# CLK_INPUT.net
KiCad netlist of a schematic drawn in Altium Designer
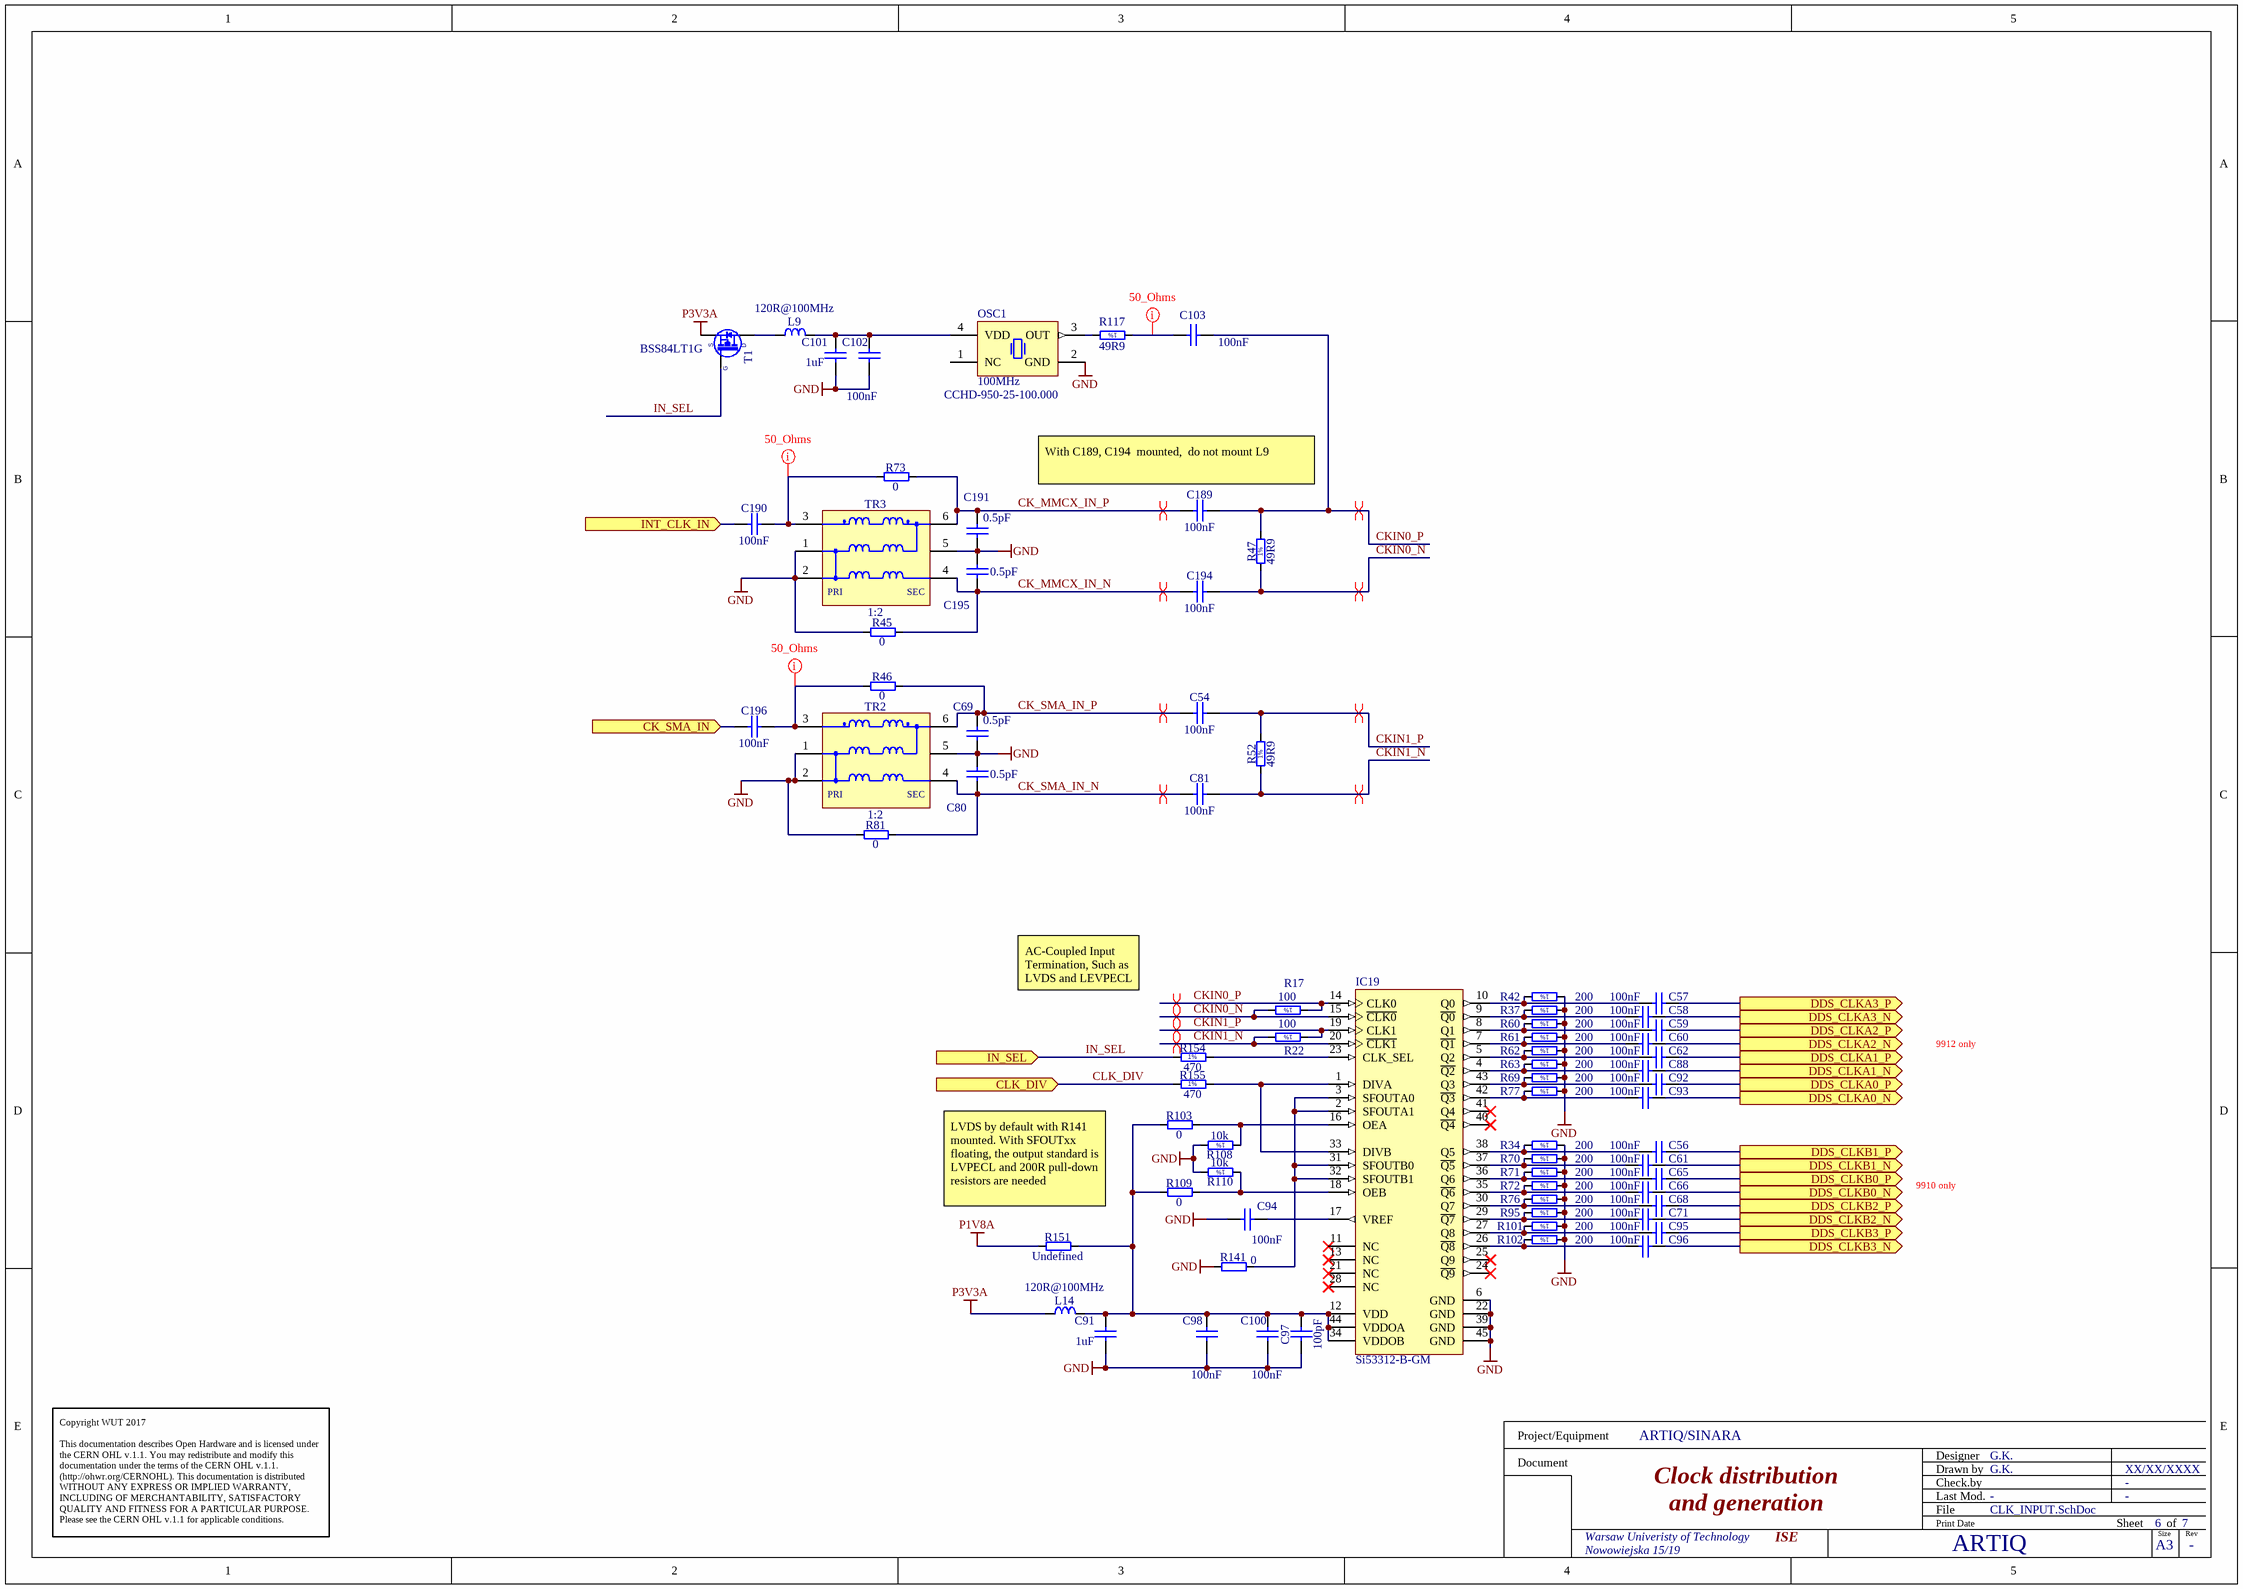
[diagram p0: CLK_INPUT.SchDoc]

(export (version "E")
  (design (tool "Eeschema 10.0.6"))
  (components
    (comp (ref "C54")
      (value "100nF")
      (footprint "CAPC1005X55N")
      (description "Non-polarised capacitor")
      (fields
        (field (name "PART NUMBER") "CC0402_100NF_16V_10%_X5R")
        (field (name "VOLTAGE") "16V")
        (field (name "AUTHOR") "CERN DEM JLC")
      )
      (libsource (lib "Capacitors") (part "Capacitor - non polarized"))
    )
    (comp (ref "C56")
      (value "100nF")
      (footprint "CAPC1005X55N")
      (description "Non-polarised capacitor")
      (fields
        (field (name "PART NUMBER") "CC0402_100NF_16V_10%_X5R")
        (field (name "VOLTAGE") "16V")
        (field (name "AUTHOR") "CERN DEM JLC")
      )
      (libsource (lib "Capacitors") (part "Capacitor - non polarized"))
    )
    (comp (ref "C57")
      (value "100nF")
      (footprint "CAPC1005X55N")
      (description "Non-polarised capacitor")
      (fields
        (field (name "PART NUMBER") "CC0402_100NF_16V_10%_X5R")
        (field (name "VOLTAGE") "16V")
        (field (name "AUTHOR") "CERN DEM JLC")
      )
      (libsource (lib "Capacitors") (part "Capacitor - non polarized"))
    )
    (comp (ref "C58")
      (value "100nF")
      (footprint "CAPC1005X55N")
      (description "Non-polarised capacitor")
      (fields
        (field (name "PART NUMBER") "CC0402_100NF_16V_10%_X5R")
        (field (name "VOLTAGE") "16V")
        (field (name "AUTHOR") "CERN DEM JLC")
      )
      (libsource (lib "Capacitors") (part "Capacitor - non polarized"))
    )
    (comp (ref "C59")
      (value "100nF")
      (footprint "CAPC1005X55N")
      (description "Non-polarised capacitor")
      (fields
        (field (name "PART NUMBER") "CC0402_100NF_16V_10%_X5R")
        (field (name "VOLTAGE") "16V")
        (field (name "AUTHOR") "CERN DEM JLC")
      )
      (libsource (lib "Capacitors") (part "Capacitor - non polarized"))
    )
    (comp (ref "C60")
      (value "100nF")
      (footprint "CAPC1005X55N")
      (description "Non-polarised capacitor")
      (fields
        (field (name "PART NUMBER") "CC0402_100NF_16V_10%_X5R")
        (field (name "VOLTAGE") "16V")
        (field (name "AUTHOR") "CERN DEM JLC")
      )
      (libsource (lib "Capacitors") (part "Capacitor - non polarized"))
    )
    (comp (ref "C61")
      (value "100nF")
      (footprint "CAPC1005X55N")
      (description "Non-polarised capacitor")
      (fields
        (field (name "PART NUMBER") "CC0402_100NF_16V_10%_X5R")
        (field (name "VOLTAGE") "16V")
        (field (name "AUTHOR") "CERN DEM JLC")
      )
      (libsource (lib "Capacitors") (part "Capacitor - non polarized"))
    )
    (comp (ref "C62")
      (value "100nF")
      (footprint "CAPC1005X55N")
      (description "Non-polarised capacitor")
      (fields
        (field (name "PART NUMBER") "CC0402_100NF_16V_10%_X5R")
        (field (name "VOLTAGE") "16V")
        (field (name "AUTHOR") "CERN DEM JLC")
      )
      (libsource (lib "Capacitors") (part "Capacitor - non polarized"))
    )
    (comp (ref "C65")
      (value "100nF")
      (footprint "CAPC1005X55N")
      (description "Non-polarised capacitor")
      (fields
        (field (name "PART NUMBER") "CC0402_100NF_16V_10%_X5R")
        (field (name "VOLTAGE") "16V")
        (field (name "AUTHOR") "CERN DEM JLC")
      )
      (libsource (lib "Capacitors") (part "Capacitor - non polarized"))
    )
    (comp (ref "C66")
      (value "100nF")
      (footprint "CAPC1005X55N")
      (description "Non-polarised capacitor")
      (fields
        (field (name "PART NUMBER") "CC0402_100NF_16V_10%_X5R")
        (field (name "VOLTAGE") "16V")
        (field (name "AUTHOR") "CERN DEM JLC")
      )
      (libsource (lib "Capacitors") (part "Capacitor - non polarized"))
    )
    (comp (ref "C68")
      (value "100nF")
      (footprint "CAPC1005X55N")
      (description "Non-polarised capacitor")
      (fields
        (field (name "PART NUMBER") "CC0402_100NF_16V_10%_X5R")
        (field (name "VOLTAGE") "16V")
        (field (name "AUTHOR") "CERN DEM JLC")
      )
      (libsource (lib "Capacitors") (part "Capacitor - non polarized"))
    )
    (comp (ref "C69")
      (value "0.5pF")
      (footprint "CAPC1005X50N")
      (description "Non-polarised capacitor")
      (fields
        (field (name "PART NUMBER") "CC0402_0.5PF_25V_0.05PF_AVX_04023J0R5ABSTR")
        (field (name "VOLTAGE") "25V")
        (field (name "AUTHOR") "CERN DEM JLC")
      )
      (libsource (lib "Capacitors") (part "Capacitor - non polarized"))
    )
    (comp (ref "C71")
      (value "100nF")
      (footprint "CAPC1005X55N")
      (description "Non-polarised capacitor")
      (fields
        (field (name "PART NUMBER") "CC0402_100NF_16V_10%_X5R")
        (field (name "VOLTAGE") "16V")
        (field (name "AUTHOR") "CERN DEM JLC")
      )
      (libsource (lib "Capacitors") (part "Capacitor - non polarized"))
    )
    (comp (ref "C80")
      (value "0.5pF")
      (footprint "CAPC1005X50N")
      (description "Non-polarised capacitor")
      (fields
        (field (name "PART NUMBER") "CC0402_0.5PF_25V_0.05PF_AVX_04023J0R5ABSTR")
        (field (name "VOLTAGE") "25V")
        (field (name "AUTHOR") "CERN DEM JLC")
      )
      (libsource (lib "Capacitors") (part "Capacitor - non polarized"))
    )
    (comp (ref "C81")
      (value "100nF")
      (footprint "CAPC1005X55N")
      (description "Non-polarised capacitor")
      (fields
        (field (name "PART NUMBER") "CC0402_100NF_16V_10%_X5R")
        (field (name "VOLTAGE") "16V")
        (field (name "AUTHOR") "CERN DEM JLC")
      )
      (libsource (lib "Capacitors") (part "Capacitor - non polarized"))
    )
    (comp (ref "C88")
      (value "100nF")
      (footprint "CAPC1005X55N")
      (description "Non-polarised capacitor")
      (fields
        (field (name "PART NUMBER") "CC0402_100NF_16V_10%_X5R")
        (field (name "VOLTAGE") "16V")
        (field (name "AUTHOR") "CERN DEM JLC")
      )
      (libsource (lib "Capacitors") (part "Capacitor - non polarized"))
    )
    (comp (ref "C91")
      (value "1uF")
      (footprint "CAPC1005X55N")
      (description "Non-polarised capacitor")
      (fields
        (field (name "PART NUMBER") "CC0402_1UF_16V_10%_X5R")
        (field (name "VOLTAGE") "16V")
        (field (name "AUTHOR") "CERN DEM JLC")
      )
      (libsource (lib "Capacitors") (part "Capacitor - non polarized"))
    )
    (comp (ref "C92")
      (value "100nF")
      (footprint "CAPC1005X55N")
      (description "Non-polarised capacitor")
      (fields
        (field (name "PART NUMBER") "CC0402_100NF_16V_10%_X5R")
        (field (name "VOLTAGE") "16V")
        (field (name "AUTHOR") "CERN DEM JLC")
      )
      (libsource (lib "Capacitors") (part "Capacitor - non polarized"))
    )
    (comp (ref "C93")
      (value "100nF")
      (footprint "CAPC1005X55N")
      (description "Non-polarised capacitor")
      (fields
        (field (name "PART NUMBER") "CC0402_100NF_16V_10%_X5R")
        (field (name "VOLTAGE") "16V")
        (field (name "AUTHOR") "CERN DEM JLC")
      )
      (libsource (lib "Capacitors") (part "Capacitor - non polarized"))
    )
    (comp (ref "C94")
      (value "100nF")
      (footprint "CAPC1005X55N")
      (description "Non-polarised capacitor")
      (fields
        (field (name "PART NUMBER") "CC0402_100NF_16V_10%_X5R")
        (field (name "VOLTAGE") "16V")
        (field (name "AUTHOR") "CERN DEM JLC")
      )
      (libsource (lib "Capacitors") (part "Capacitor - non polarized"))
    )
    (comp (ref "C95")
      (value "100nF")
      (footprint "CAPC1005X55N")
      (description "Non-polarised capacitor")
      (fields
        (field (name "PART NUMBER") "CC0402_100NF_16V_10%_X5R")
        (field (name "VOLTAGE") "16V")
        (field (name "AUTHOR") "CERN DEM JLC")
      )
      (libsource (lib "Capacitors") (part "Capacitor - non polarized"))
    )
    (comp (ref "C96")
      (value "100nF")
      (footprint "CAPC1005X55N")
      (description "Non-polarised capacitor")
      (fields
        (field (name "PART NUMBER") "CC0402_100NF_16V_10%_X5R")
        (field (name "VOLTAGE") "16V")
        (field (name "AUTHOR") "CERN DEM JLC")
      )
      (libsource (lib "Capacitors") (part "Capacitor - non polarized"))
    )
    (comp (ref "C97")
      (value "100pF")
      (footprint "CAPC1005X55N")
      (description "Non-polarised capacitor")
      (fields
        (field (name "PART NUMBER") "CC0402_100PF_50V_5%_C0G")
        (field (name "VOLTAGE") "50V")
        (field (name "AUTHOR") "CERN DEM JLC")
      )
      (libsource (lib "Capacitors") (part "Capacitor - non polarized"))
    )
    (comp (ref "C98")
      (value "100nF")
      (footprint "CAPC1005X55N")
      (description "Non-polarised capacitor")
      (fields
        (field (name "PART NUMBER") "CC0402_100NF_16V_10%_X5R")
        (field (name "VOLTAGE") "16V")
        (field (name "AUTHOR") "CERN DEM JLC")
      )
      (libsource (lib "Capacitors") (part "Capacitor - non polarized"))
    )
    (comp (ref "C100")
      (value "100nF")
      (footprint "CAPC1005X55N")
      (description "Non-polarised capacitor")
      (fields
        (field (name "PART NUMBER") "CC0402_100NF_16V_10%_X5R")
        (field (name "VOLTAGE") "16V")
        (field (name "AUTHOR") "CERN DEM JLC")
      )
      (libsource (lib "Capacitors") (part "Capacitor - non polarized"))
    )
    (comp (ref "C101")
      (value "1uF")
      (footprint "CAPC1005X55N")
      (description "Non-polarised capacitor")
      (fields
        (field (name "PART NUMBER") "CC0402_1UF_16V_10%_X5R")
        (field (name "VOLTAGE") "16V")
        (field (name "AUTHOR") "CERN DEM JLC")
      )
      (libsource (lib "Capacitors") (part "Capacitor - non polarized"))
    )
    (comp (ref "C102")
      (value "100nF")
      (footprint "CAPC1005X55N")
      (description "Non-polarised capacitor")
      (fields
        (field (name "PART NUMBER") "CC0402_100NF_16V_10%_X5R")
        (field (name "VOLTAGE") "16V")
        (field (name "AUTHOR") "CERN DEM JLC")
      )
      (libsource (lib "Capacitors") (part "Capacitor - non polarized"))
    )
    (comp (ref "C103")
      (value "100nF")
      (footprint "CAPC1005X55N")
      (description "Non-polarised capacitor")
      (fields
        (field (name "PART NUMBER") "CC0402_100NF_16V_10%_X5R")
        (field (name "VOLTAGE") "16V")
        (field (name "AUTHOR") "CERN DEM JLC")
      )
      (libsource (lib "Capacitors") (part "Capacitor - non polarized"))
    )
    (comp (ref "C189")
      (value "100nF")
      (footprint "CAPC1005X55N")
      (description "Non-polarised capacitor")
      (fields
        (field (name "PART NUMBER") "CC0402_100NF_16V_10%_X5R")
        (field (name "VOLTAGE") "16V")
        (field (name "AUTHOR") "CERN DEM JLC")
      )
      (libsource (lib "Capacitors") (part "Capacitor - non polarized"))
    )
    (comp (ref "C190")
      (value "100nF")
      (footprint "CAPC1005X55N")
      (description "Non-polarised capacitor")
      (fields
        (field (name "PART NUMBER") "CC0402_100NF_16V_10%_X5R")
        (field (name "VOLTAGE") "16V")
        (field (name "AUTHOR") "CERN DEM JLC")
      )
      (libsource (lib "Capacitors") (part "Capacitor - non polarized"))
    )
    (comp (ref "C191")
      (value "0.5pF")
      (footprint "CAPC1005X50N")
      (description "Non-polarised capacitor")
      (fields
        (field (name "PART NUMBER") "CC0402_0.5PF_25V_0.05PF_AVX_04023J0R5ABSTR")
        (field (name "VOLTAGE") "25V")
        (field (name "AUTHOR") "CERN DEM JLC")
      )
      (libsource (lib "Capacitors") (part "Capacitor - non polarized"))
    )
    (comp (ref "C194")
      (value "100nF")
      (footprint "CAPC1005X55N")
      (description "Non-polarised capacitor")
      (fields
        (field (name "PART NUMBER") "CC0402_100NF_16V_10%_X5R")
        (field (name "VOLTAGE") "16V")
        (field (name "AUTHOR") "CERN DEM JLC")
      )
      (libsource (lib "Capacitors") (part "Capacitor - non polarized"))
    )
    (comp (ref "C195")
      (value "0.5pF")
      (footprint "CAPC1005X50N")
      (description "Non-polarised capacitor")
      (fields
        (field (name "PART NUMBER") "CC0402_0.5PF_25V_0.05PF_AVX_04023J0R5ABSTR")
        (field (name "VOLTAGE") "25V")
        (field (name "AUTHOR") "CERN DEM JLC")
      )
      (libsource (lib "Capacitors") (part "Capacitor - non polarized"))
    )
    (comp (ref "C196")
      (value "100nF")
      (footprint "CAPC1005X55N")
      (description "Non-polarised capacitor")
      (fields
        (field (name "PART NUMBER") "CC0402_100NF_16V_10%_X5R")
        (field (name "VOLTAGE") "16V")
        (field (name "AUTHOR") "CERN DEM JLC")
      )
      (libsource (lib "Capacitors") (part "Capacitor - non polarized"))
    )
    (comp (ref "IC19")
      (value "Si53312-B-GM")
      (footprint "SLAB-QFN-44-2800x2800TP_N")
      (fields (field (name "MANUFACTURER") "Silicon Labs"))
      (libsource (lib "Altium Content Vault") (part "SLAB-Si53312-QFN-44-45"))
    )
    (comp (ref "L9")
      (value "120R@100MHz")
      (footprint "INDC1608X95N")
      (description "Inductor")
      (fields
        (field (name "PART NUMBER") "IND0603_MURATA_BLM18PG121SN1D")
        (field (name "POWER") "2A")
        (field (name "AUTHOR") "CERN DEM BC")
      )
      (libsource (lib "Inductors & Transformers") (part "Inductor"))
    )
    (comp (ref "L14")
      (value "120R@100MHz")
      (footprint "INDC1608X95N")
      (description "Inductor")
      (fields
        (field (name "PART NUMBER") "IND0603_MURATA_BLM18PG121SN1D")
        (field (name "POWER") "2A")
        (field (name "AUTHOR") "CERN DEM BC")
      )
      (libsource (lib "Inductors & Transformers") (part "Inductor"))
    )
    (comp (ref "OSC1")
      (value "100MHz")
      (footprint "OSC_CRYSTEK_CCHD-950")
      (description "100MHz low noise oscillator")
      (fields
        (field (name "PART NUMBER") "OSC_100MHZ_CRYSTEK_CCHD-950-25-100.000")
        (field (name "MANUFACTURER") "CRYSTEK CRYSTAL")
        (field (name "MANUFACTURER PART NUMBER") "CCHD-950-25-100.000")
        (field (name "AUTHOR") "GK")
      )
      (libsource (lib "LIBRARY_SCH") (part "OSC_CCHD-950"))
    )
    (comp (ref "R17")
      (value "100")
      (footprint "RESC1005X40N")
      (description "Resistor - 1%")
      (fields
        (field (name "PART NUMBER") "R0402_100R_1%_0.0625W_100PPM")
        (field (name "POWER") "0.0625W")
        (field (name "AUTHOR") "CERN DEM JLC")
      )
      (libsource (lib "Resistors") (part "Resistor - 1%"))
    )
    (comp (ref "R22")
      (value "100")
      (footprint "RESC1005X40N")
      (description "Resistor - 1%")
      (fields
        (field (name "PART NUMBER") "R0402_100R_1%_0.0625W_100PPM")
        (field (name "POWER") "0.0625W")
        (field (name "AUTHOR") "CERN DEM JLC")
      )
      (libsource (lib "Resistors") (part "Resistor - 1%"))
    )
    (comp (ref "R34")
      (value "200")
      (footprint "RESC1005X40N")
      (description "Resistor - 1%")
      (fields
        (field (name "PART NUMBER") "R0402_200R_1%_0.0625W_100PPM")
        (field (name "POWER") "0.0625W")
        (field (name "AUTHOR") "CERN DEM JLC")
      )
      (libsource (lib "Resistors") (part "Resistor - 1%"))
    )
    (comp (ref "R37")
      (value "200")
      (footprint "RESC1005X40N")
      (description "Resistor - 1%")
      (fields
        (field (name "PART NUMBER") "R0402_200R_1%_0.0625W_100PPM")
        (field (name "POWER") "0.0625W")
        (field (name "AUTHOR") "CERN DEM JLC")
      )
      (libsource (lib "Resistors") (part "Resistor - 1%"))
    )
    (comp (ref "R42")
      (value "200")
      (footprint "RESC1005X40N")
      (description "Resistor - 1%")
      (fields
        (field (name "PART NUMBER") "R0402_200R_1%_0.0625W_100PPM")
        (field (name "POWER") "0.0625W")
        (field (name "AUTHOR") "CERN DEM JLC")
      )
      (libsource (lib "Resistors") (part "Resistor - 1%"))
    )
    (comp (ref "R45")
      (value "0")
      (footprint "RESC1005X40N")
      (description "Resistor")
      (fields
        (field (name "PART NUMBER") "R0402_0R_JUMPER")
        (field (name "MANUFACTURER") "GENERIC")
        (field (name "AUTHOR") "CERN DEM JLC")
      )
      (libsource (lib "Resistors") (part "Resistor"))
    )
    (comp (ref "R46")
      (value "0")
      (footprint "RESC1005X40N")
      (description "Resistor")
      (fields
        (field (name "PART NUMBER") "R0402_0R_JUMPER")
        (field (name "MANUFACTURER") "GENERIC")
        (field (name "AUTHOR") "CERN DEM JLC")
      )
      (libsource (lib "Resistors") (part "Resistor"))
    )
    (comp (ref "R47")
      (value "49R9")
      (footprint "RESC1005X40N")
      (description "Resistor - 1%")
      (fields
        (field (name "PART NUMBER") "R0402_49R9_1%_0.0625W_100PPM")
        (field (name "POWER") "0.0625W")
        (field (name "AUTHOR") "CERN DEM JLC")
      )
      (libsource (lib "Resistors") (part "Resistor - 1%"))
    )
    (comp (ref "R52")
      (value "49R9")
      (footprint "RESC1005X40N")
      (description "Resistor - 1%")
      (fields
        (field (name "PART NUMBER") "R0402_49R9_1%_0.0625W_100PPM")
        (field (name "POWER") "0.0625W")
        (field (name "AUTHOR") "CERN DEM JLC")
      )
      (libsource (lib "Resistors") (part "Resistor - 1%"))
    )
    (comp (ref "R60")
      (value "200")
      (footprint "RESC1005X40N")
      (description "Resistor - 1%")
      (fields
        (field (name "PART NUMBER") "R0402_200R_1%_0.0625W_100PPM")
        (field (name "POWER") "0.0625W")
        (field (name "AUTHOR") "CERN DEM JLC")
      )
      (libsource (lib "Resistors") (part "Resistor - 1%"))
    )
    (comp (ref "R61")
      (value "200")
      (footprint "RESC1005X40N")
      (description "Resistor - 1%")
      (fields
        (field (name "PART NUMBER") "R0402_200R_1%_0.0625W_100PPM")
        (field (name "POWER") "0.0625W")
        (field (name "AUTHOR") "CERN DEM JLC")
      )
      (libsource (lib "Resistors") (part "Resistor - 1%"))
    )
    (comp (ref "R62")
      (value "200")
      (footprint "RESC1005X40N")
      (description "Resistor - 1%")
      (fields
        (field (name "PART NUMBER") "R0402_200R_1%_0.0625W_100PPM")
        (field (name "POWER") "0.0625W")
        (field (name "AUTHOR") "CERN DEM JLC")
      )
      (libsource (lib "Resistors") (part "Resistor - 1%"))
    )
    (comp (ref "R63")
      (value "200")
      (footprint "RESC1005X40N")
      (description "Resistor - 1%")
      (fields
        (field (name "PART NUMBER") "R0402_200R_1%_0.0625W_100PPM")
        (field (name "POWER") "0.0625W")
        (field (name "AUTHOR") "CERN DEM JLC")
      )
      (libsource (lib "Resistors") (part "Resistor - 1%"))
    )
    (comp (ref "R69")
      (value "200")
      (footprint "RESC1005X40N")
      (description "Resistor - 1%")
      (fields
        (field (name "PART NUMBER") "R0402_200R_1%_0.0625W_100PPM")
        (field (name "POWER") "0.0625W")
        (field (name "AUTHOR") "CERN DEM JLC")
      )
      (libsource (lib "Resistors") (part "Resistor - 1%"))
    )
    (comp (ref "R70")
      (value "200")
      (footprint "RESC1005X40N")
      (description "Resistor - 1%")
      (fields
        (field (name "PART NUMBER") "R0402_200R_1%_0.0625W_100PPM")
        (field (name "POWER") "0.0625W")
        (field (name "AUTHOR") "CERN DEM JLC")
      )
      (libsource (lib "Resistors") (part "Resistor - 1%"))
    )
    (comp (ref "R71")
      (value "200")
      (footprint "RESC1005X40N")
      (description "Resistor - 1%")
      (fields
        (field (name "PART NUMBER") "R0402_200R_1%_0.0625W_100PPM")
        (field (name "POWER") "0.0625W")
        (field (name "AUTHOR") "CERN DEM JLC")
      )
      (libsource (lib "Resistors") (part "Resistor - 1%"))
    )
    (comp (ref "R72")
      (value "200")
      (footprint "RESC1005X40N")
      (description "Resistor - 1%")
      (fields
        (field (name "PART NUMBER") "R0402_200R_1%_0.0625W_100PPM")
        (field (name "POWER") "0.0625W")
        (field (name "AUTHOR") "CERN DEM JLC")
      )
      (libsource (lib "Resistors") (part "Resistor - 1%"))
    )
    (comp (ref "R73")
      (value "0")
      (footprint "RESC1005X40N")
      (description "Resistor")
      (fields
        (field (name "PART NUMBER") "R0402_0R_JUMPER")
        (field (name "MANUFACTURER") "GENERIC")
        (field (name "AUTHOR") "CERN DEM JLC")
      )
      (libsource (lib "Resistors") (part "Resistor"))
    )
    (comp (ref "R76")
      (value "200")
      (footprint "RESC1005X40N")
      (description "Resistor - 1%")
      (fields
        (field (name "PART NUMBER") "R0402_200R_1%_0.0625W_100PPM")
        (field (name "POWER") "0.0625W")
        (field (name "AUTHOR") "CERN DEM JLC")
      )
      (libsource (lib "Resistors") (part "Resistor - 1%"))
    )
    (comp (ref "R77")
      (value "200")
      (footprint "RESC1005X40N")
      (description "Resistor - 1%")
      (fields
        (field (name "PART NUMBER") "R0402_200R_1%_0.0625W_100PPM")
        (field (name "POWER") "0.0625W")
        (field (name "AUTHOR") "CERN DEM JLC")
      )
      (libsource (lib "Resistors") (part "Resistor - 1%"))
    )
    (comp (ref "R81")
      (value "0")
      (footprint "RESC1005X40N")
      (description "Resistor")
      (fields
        (field (name "PART NUMBER") "R0402_0R_JUMPER")
        (field (name "MANUFACTURER") "GENERIC")
        (field (name "AUTHOR") "CERN DEM JLC")
      )
      (libsource (lib "Resistors") (part "Resistor"))
    )
    (comp (ref "R95")
      (value "200")
      (footprint "RESC1005X40N")
      (description "Resistor - 1%")
      (fields
        (field (name "PART NUMBER") "R0402_200R_1%_0.0625W_100PPM")
        (field (name "POWER") "0.0625W")
        (field (name "AUTHOR") "CERN DEM JLC")
      )
      (libsource (lib "Resistors") (part "Resistor - 1%"))
    )
    (comp (ref "R101")
      (value "200")
      (footprint "RESC1005X40N")
      (description "Resistor - 1%")
      (fields
        (field (name "PART NUMBER") "R0402_200R_1%_0.0625W_100PPM")
        (field (name "POWER") "0.0625W")
        (field (name "AUTHOR") "CERN DEM JLC")
      )
      (libsource (lib "Resistors") (part "Resistor - 1%"))
    )
    (comp (ref "R102")
      (value "200")
      (footprint "RESC1005X40N")
      (description "Resistor - 1%")
      (fields
        (field (name "PART NUMBER") "R0402_200R_1%_0.0625W_100PPM")
        (field (name "POWER") "0.0625W")
        (field (name "AUTHOR") "CERN DEM JLC")
      )
      (libsource (lib "Resistors") (part "Resistor - 1%"))
    )
    (comp (ref "R103")
      (value "0")
      (footprint "RESC1608X55N")
      (description "Resistor")
      (fields
        (field (name "PART NUMBER") "R0603_0R_JUMPER")
        (field (name "MANUFACTURER") "GENERIC")
        (field (name "AUTHOR") "CERN DEM JLC")
      )
      (libsource (lib "Resistors") (part "Resistor"))
    )
    (comp (ref "R108")
      (value "10k")
      (footprint "RESC1005X40N")
      (description "Resistor - 1%")
      (fields
        (field (name "PART NUMBER") "R0402_10K_1%_0.0625W_100PPM")
        (field (name "POWER") "0.0625W")
        (field (name "AUTHOR") "CERN DEM JLC")
      )
      (libsource (lib "Resistors") (part "Resistor - 1%"))
    )
    (comp (ref "R109")
      (value "0")
      (footprint "RESC1608X55N")
      (description "Resistor")
      (fields
        (field (name "PART NUMBER") "R0603_0R_JUMPER")
        (field (name "MANUFACTURER") "GENERIC")
        (field (name "AUTHOR") "CERN DEM JLC")
      )
      (libsource (lib "Resistors") (part "Resistor"))
    )
    (comp (ref "R110")
      (value "10k")
      (footprint "RESC1005X40N")
      (description "Resistor - 1%")
      (fields
        (field (name "PART NUMBER") "R0402_10K_1%_0.0625W_100PPM")
        (field (name "POWER") "0.0625W")
        (field (name "AUTHOR") "CERN DEM JLC")
      )
      (libsource (lib "Resistors") (part "Resistor - 1%"))
    )
    (comp (ref "R117")
      (value "49R9")
      (footprint "RESC1005X40N")
      (description "Resistor - 1%")
      (fields
        (field (name "PART NUMBER") "R0402_49R9_1%_0.0625W_100PPM")
        (field (name "POWER") "0.0625W")
        (field (name "AUTHOR") "CERN DEM JLC")
      )
      (libsource (lib "Resistors") (part "Resistor - 1%"))
    )
    (comp (ref "R141")
      (value "0")
      (footprint "RESC1608X55N")
      (description "Resistor")
      (fields
        (field (name "PART NUMBER") "R0603_0R_JUMPER")
        (field (name "MANUFACTURER") "GENERIC")
        (field (name "AUTHOR") "CERN DEM JLC")
      )
      (libsource (lib "Resistors") (part "Resistor"))
    )
    (comp (ref "R151")
      (value "Undefined")
      (footprint "RESC1608X55N")
      (description "Resistor")
      (fields (field (name "PART NUMBER") "R0603_NO-VALUE") (field (name "AUTHOR") "CERN DEM JLC"))
      (libsource (lib "Resistors") (part "Resistor"))
    )
    (comp (ref "R154")
      (value "470")
      (footprint "RESC1005X40N")
      (description "Resistor - 1%")
      (fields
        (field (name "PART NUMBER") "R0402_470R_1%_0.0625W_100PPM")
        (field (name "POWER") "0.0625W")
        (field (name "AUTHOR") "CERN DEM JLC")
      )
      (libsource (lib "Resistors") (part "Resistor - 1%"))
    )
    (comp (ref "R155")
      (value "470")
      (footprint "RESC1005X40N")
      (description "Resistor - 1%")
      (fields
        (field (name "PART NUMBER") "R0402_470R_1%_0.0625W_100PPM")
        (field (name "POWER") "0.0625W")
        (field (name "AUTHOR") "CERN DEM JLC")
      )
      (libsource (lib "Resistors") (part "Resistor - 1%"))
    )
    (comp (ref "T1")
      (value "BSS84LT1G")
      (footprint "SOT95P240X110-3N")
      (description "P-CHANNEL MOSFET WITH DIODE")
      (fields (field (name "MANUFACTURER") "ON SEMICONDUCTOR") (field (name "AUTHOR") "CERN DEM JLC"))
      (libsource (lib "ICs And Semiconductors") (part "P-MOSFET-D 1G 2S 3D"))
    )
    (comp (ref "TR2")
      (value "1:2")
      (footprint "XFMR_MINI-CIRCUITS_DB1627")
      (description "50 OHMS 10 to 4000 MHz RF Transformer")
      (fields
        (field (name "PART NUMBER") "XFMR_MINI-CIRCUITS_TCM2-43X+")
        (field (name "POWER") "0.4W")
        (field (name "AUTHOR") "CERN DEM BC")
      )
      (libsource (lib "Inductors & Transformers") (part "XFMR_MINI-CIRCUITS_TCM2-43X"))
    )
    (comp (ref "TR3")
      (value "1:2")
      (footprint "XFMR_MINI-CIRCUITS_DB1627")
      (description "50 OHMS 10 to 4000 MHz RF Transformer")
      (fields
        (field (name "PART NUMBER") "XFMR_MINI-CIRCUITS_TCM2-43X+")
        (field (name "POWER") "0.4W")
        (field (name "AUTHOR") "CERN DEM BC")
      )
      (libsource (lib "Inductors & Transformers") (part "XFMR_MINI-CIRCUITS_TCM2-43X"))
    )
  )
  (nets
    (net (code "1") (name "/CKIN0_N") (class "Default")
      (node (ref "C194") (pin "2") (pinfunction "2_2") (pintype "passive"))
      (node (ref "IC19") (pin "15") (pinfunction "~{CLK0}_15") (pintype "input"))
      (node (ref "R17") (pin "2") (pinfunction "2_2") (pintype "passive"))
      (node (ref "R47") (pin "1") (pinfunction "1_1") (pintype "passive"))
    )
    (net (code "2") (name "/CKIN0_P") (class "Default")
      (node (ref "C103") (pin "1") (pinfunction "1_1") (pintype "passive"))
      (node (ref "C189") (pin "2") (pinfunction "2_2") (pintype "passive"))
      (node (ref "IC19") (pin "14") (pinfunction "CLK0_14") (pintype "input"))
      (node (ref "R17") (pin "1") (pinfunction "1_1") (pintype "passive"))
      (node (ref "R47") (pin "2") (pinfunction "2_2") (pintype "passive"))
    )
    (net (code "3") (name "/CKIN1_N") (class "Default")
      (node (ref "C81") (pin "2") (pinfunction "2_2") (pintype "passive"))
      (node (ref "IC19") (pin "20") (pinfunction "~{CLK1}_20") (pintype "input"))
      (node (ref "R22") (pin "2") (pinfunction "2_2") (pintype "passive"))
      (node (ref "R52") (pin "1") (pinfunction "1_1") (pintype "passive"))
    )
    (net (code "4") (name "/CKIN1_P") (class "Default")
      (node (ref "C54") (pin "2") (pinfunction "2_2") (pintype "passive"))
      (node (ref "IC19") (pin "19") (pinfunction "CLK1_19") (pintype "input"))
      (node (ref "R22") (pin "1") (pinfunction "1_1") (pintype "passive"))
      (node (ref "R52") (pin "2") (pinfunction "2_2") (pintype "passive"))
    )
    (net (code "5") (name "/CK_MMCX_IN_N") (class "Default")
      (node (ref "C194") (pin "1") (pinfunction "1_1") (pintype "passive"))
      (node (ref "C195") (pin "1") (pinfunction "1_1") (pintype "passive"))
      (node (ref "R45") (pin "2") (pinfunction "2_2") (pintype "passive"))
      (node (ref "TR3") (pin "4") (pinfunction "S1_4") (pintype "passive"))
    )
    (net (code "6") (name "/CK_MMCX_IN_P") (class "Default")
      (node (ref "C189") (pin "1") (pinfunction "1_1") (pintype "passive"))
      (node (ref "C191") (pin "2") (pinfunction "2_2") (pintype "passive"))
      (node (ref "R73") (pin "2") (pinfunction "2_2") (pintype "passive"))
      (node (ref "TR3") (pin "6") (pinfunction "S1_6") (pintype "passive"))
    )
    (net (code "7") (name "/CK_SMA_IN") (class "Default")
      (node (ref "C196") (pin "1") (pinfunction "1_1") (pintype "passive"))
    )
    (net (code "8") (name "/CK_SMA_IN_N") (class "Default")
      (node (ref "C80") (pin "1") (pinfunction "1_1") (pintype "passive"))
      (node (ref "C81") (pin "1") (pinfunction "1_1") (pintype "passive"))
      (node (ref "R81") (pin "2") (pinfunction "2_2") (pintype "passive"))
      (node (ref "TR2") (pin "4") (pinfunction "S1_4") (pintype "passive"))
    )
    (net (code "9") (name "/CK_SMA_IN_P") (class "Default")
      (node (ref "C54") (pin "1") (pinfunction "1_1") (pintype "passive"))
      (node (ref "C69") (pin "2") (pinfunction "2_2") (pintype "passive"))
      (node (ref "R46") (pin "2") (pinfunction "2_2") (pintype "passive"))
      (node (ref "TR2") (pin "6") (pinfunction "S1_6") (pintype "passive"))
    )
    (net (code "10") (name "/CLK_DIV") (class "Default")
      (node (ref "R155") (pin "1") (pinfunction "1_1") (pintype "passive"))
    )
    (net (code "11") (name "/DDS_CLKA0_N") (class "Default")
      (node (ref "C93") (pin "1") (pinfunction "1_1") (pintype "passive"))
    )
    (net (code "12") (name "/DDS_CLKA0_P") (class "Default")
      (node (ref "C92") (pin "1") (pinfunction "1_1") (pintype "passive"))
    )
    (net (code "13") (name "/DDS_CLKA1_N") (class "Default")
      (node (ref "C88") (pin "1") (pinfunction "1_1") (pintype "passive"))
    )
    (net (code "14") (name "/DDS_CLKA1_P") (class "Default")
      (node (ref "C62") (pin "1") (pinfunction "1_1") (pintype "passive"))
    )
    (net (code "15") (name "/DDS_CLKA2_N") (class "Default")
      (node (ref "C60") (pin "1") (pinfunction "1_1") (pintype "passive"))
    )
    (net (code "16") (name "/DDS_CLKA2_P") (class "Default")
      (node (ref "C59") (pin "1") (pinfunction "1_1") (pintype "passive"))
    )
    (net (code "17") (name "/DDS_CLKA3_N") (class "Default")
      (node (ref "C58") (pin "1") (pinfunction "1_1") (pintype "passive"))
    )
    (net (code "18") (name "/DDS_CLKA3_P") (class "Default")
      (node (ref "C57") (pin "1") (pinfunction "1_1") (pintype "passive"))
    )
    (net (code "19") (name "/DDS_CLKB0_N") (class "Default")
      (node (ref "C66") (pin "1") (pinfunction "1_1") (pintype "passive"))
    )
    (net (code "20") (name "/DDS_CLKB0_P") (class "Default")
      (node (ref "C65") (pin "1") (pinfunction "1_1") (pintype "passive"))
    )
    (net (code "21") (name "/DDS_CLKB1_N") (class "Default")
      (node (ref "C61") (pin "1") (pinfunction "1_1") (pintype "passive"))
    )
    (net (code "22") (name "/DDS_CLKB1_P") (class "Default")
      (node (ref "C56") (pin "1") (pinfunction "1_1") (pintype "passive"))
    )
    (net (code "23") (name "/DDS_CLKB2_N") (class "Default")
      (node (ref "C71") (pin "1") (pinfunction "1_1") (pintype "passive"))
    )
    (net (code "24") (name "/DDS_CLKB2_P") (class "Default")
      (node (ref "C68") (pin "1") (pinfunction "1_1") (pintype "passive"))
    )
    (net (code "25") (name "/DDS_CLKB3_N") (class "Default")
      (node (ref "C96") (pin "1") (pinfunction "1_1") (pintype "passive"))
    )
    (net (code "26") (name "/DDS_CLKB3_P") (class "Default")
      (node (ref "C95") (pin "1") (pinfunction "1_1") (pintype "passive"))
    )
    (net (code "27") (name "/INT_CLK_IN") (class "Default")
      (node (ref "C190") (pin "1") (pinfunction "1_1") (pintype "passive"))
    )
    (net (code "28") (name "/IN_SEL") (class "Default")
      (node (ref "R154") (pin "1") (pinfunction "1_1") (pintype "passive"))
      (node (ref "T1") (pin "1") (pinfunction "G_1") (pintype "passive"))
    )
    (net (code "29") (name "GND") (class "Default")
      (node (ref "C100") (pin "1") (pinfunction "1_1") (pintype "passive"))
      (node (ref "C101") (pin "1") (pinfunction "1_1") (pintype "passive"))
      (node (ref "C102") (pin "1") (pinfunction "1_1") (pintype "passive"))
      (node (ref "C191") (pin "1") (pinfunction "1_1") (pintype "passive"))
      (node (ref "C195") (pin "2") (pinfunction "2_2") (pintype "passive"))
      (node (ref "C69") (pin "1") (pinfunction "1_1") (pintype "passive"))
      (node (ref "C80") (pin "2") (pinfunction "2_2") (pintype "passive"))
      (node (ref "C91") (pin "1") (pinfunction "1_1") (pintype "passive"))
      (node (ref "C94") (pin "1") (pinfunction "1_1") (pintype "passive"))
      (node (ref "C97") (pin "1") (pinfunction "1_1") (pintype "passive"))
      (node (ref "C98") (pin "1") (pinfunction "1_1") (pintype "passive"))
      (node (ref "IC19") (pin "22") (pinfunction "GND_22") (pintype "power_in"))
      (node (ref "IC19") (pin "39") (pinfunction "GND_39") (pintype "power_in"))
      (node (ref "IC19") (pin "45") (pinfunction "GND_45") (pintype "power_in"))
      (node (ref "IC19") (pin "6") (pinfunction "GND_6") (pintype "power_in"))
      (node (ref "OSC1") (pin "2") (pinfunction "GND_2") (pintype "power_in"))
      (node (ref "R101") (pin "1") (pinfunction "1_1") (pintype "passive"))
      (node (ref "R102") (pin "1") (pinfunction "1_1") (pintype "passive"))
      (node (ref "R108") (pin "2") (pinfunction "2_2") (pintype "passive"))
      (node (ref "R110") (pin "2") (pinfunction "2_2") (pintype "passive"))
      (node (ref "R141") (pin "1") (pinfunction "1_1") (pintype "passive"))
      (node (ref "R34") (pin "1") (pinfunction "1_1") (pintype "passive"))
      (node (ref "R37") (pin "1") (pinfunction "1_1") (pintype "passive"))
      (node (ref "R42") (pin "1") (pinfunction "1_1") (pintype "passive"))
      (node (ref "R45") (pin "1") (pinfunction "1_1") (pintype "passive"))
      (node (ref "R60") (pin "1") (pinfunction "1_1") (pintype "passive"))
      (node (ref "R61") (pin "1") (pinfunction "1_1") (pintype "passive"))
      (node (ref "R62") (pin "1") (pinfunction "1_1") (pintype "passive"))
      (node (ref "R63") (pin "1") (pinfunction "1_1") (pintype "passive"))
      (node (ref "R69") (pin "1") (pinfunction "1_1") (pintype "passive"))
      (node (ref "R70") (pin "1") (pinfunction "1_1") (pintype "passive"))
      (node (ref "R71") (pin "1") (pinfunction "1_1") (pintype "passive"))
      (node (ref "R72") (pin "1") (pinfunction "1_1") (pintype "passive"))
      (node (ref "R76") (pin "1") (pinfunction "1_1") (pintype "passive"))
      (node (ref "R77") (pin "1") (pinfunction "1_1") (pintype "passive"))
      (node (ref "R81") (pin "1") (pinfunction "1_1") (pintype "passive"))
      (node (ref "R95") (pin "1") (pinfunction "1_1") (pintype "passive"))
      (node (ref "TR2") (pin "1") (pinfunction "P1_1") (pintype "passive"))
      (node (ref "TR2") (pin "2") (pinfunction "P1_2") (pintype "passive"))
      (node (ref "TR2") (pin "5") (pinfunction "NC_5") (pintype "passive"))
      (node (ref "TR3") (pin "1") (pinfunction "P1_1") (pintype "passive"))
      (node (ref "TR3") (pin "2") (pinfunction "P1_2") (pintype "passive"))
      (node (ref "TR3") (pin "5") (pinfunction "NC_5") (pintype "passive"))
    )
    (net (code "30") (name "Net-(C103-Pad2)") (class "Default")
      (node (ref "C103") (pin "2") (pinfunction "2_2") (pintype "passive"))
      (node (ref "R117") (pin "1") (pinfunction "1_1") (pintype "passive"))
    )
    (net (code "31") (name "Net-(C190-Pad2)") (class "Default")
      (node (ref "C190") (pin "2") (pinfunction "2_2") (pintype "passive"))
      (node (ref "R73") (pin "1") (pinfunction "1_1") (pintype "passive"))
      (node (ref "TR3") (pin "3") (pinfunction "P1_3") (pintype "passive"))
    )
    (net (code "32") (name "Net-(C196-Pad2)") (class "Default")
      (node (ref "C196") (pin "2") (pinfunction "2_2") (pintype "passive"))
      (node (ref "R46") (pin "1") (pinfunction "1_1") (pintype "passive"))
      (node (ref "TR2") (pin "3") (pinfunction "P1_3") (pintype "passive"))
    )
    (net (code "33") (name "Net-(IC19-CLK_SEL)") (class "Default")
      (node (ref "IC19") (pin "23") (pinfunction "CLK_SEL_23") (pintype "input"))
      (node (ref "R154") (pin "2") (pinfunction "2_2") (pintype "passive"))
    )
    (net (code "34") (name "Net-(IC19-DIVA)") (class "Default")
      (node (ref "IC19") (pin "1") (pinfunction "DIVA_1") (pintype "input"))
      (node (ref "IC19") (pin "33") (pinfunction "DIVB_33") (pintype "input"))
      (node (ref "R155") (pin "2") (pinfunction "2_2") (pintype "passive"))
    )
    (net (code "35") (name "Net-(IC19-OEA)") (class "Default")
      (node (ref "IC19") (pin "16") (pinfunction "OEA_16") (pintype "input"))
      (node (ref "R103") (pin "2") (pinfunction "2_2") (pintype "passive"))
      (node (ref "R108") (pin "1") (pinfunction "1_1") (pintype "passive"))
    )
    (net (code "36") (name "Net-(IC19-OEB)") (class "Default")
      (node (ref "IC19") (pin "18") (pinfunction "OEB_18") (pintype "input"))
      (node (ref "R109") (pin "2") (pinfunction "2_2") (pintype "passive"))
      (node (ref "R110") (pin "1") (pinfunction "1_1") (pintype "passive"))
    )
    (net (code "37") (name "Net-(IC19-Q0)") (class "Default")
      (node (ref "C57") (pin "2") (pinfunction "2_2") (pintype "passive"))
      (node (ref "IC19") (pin "10") (pinfunction "Q0_10") (pintype "output"))
      (node (ref "R42") (pin "2") (pinfunction "2_2") (pintype "passive"))
    )
    (net (code "38") (name "Net-(IC19-Q1)") (class "Default")
      (node (ref "C59") (pin "2") (pinfunction "2_2") (pintype "passive"))
      (node (ref "IC19") (pin "8") (pinfunction "Q1_8") (pintype "output"))
      (node (ref "R60") (pin "2") (pinfunction "2_2") (pintype "passive"))
    )
    (net (code "39") (name "Net-(IC19-Q2)") (class "Default")
      (node (ref "C62") (pin "2") (pinfunction "2_2") (pintype "passive"))
      (node (ref "IC19") (pin "5") (pinfunction "Q2_5") (pintype "output"))
      (node (ref "R62") (pin "2") (pinfunction "2_2") (pintype "passive"))
    )
    (net (code "40") (name "Net-(IC19-Q3)") (class "Default")
      (node (ref "C92") (pin "2") (pinfunction "2_2") (pintype "passive"))
      (node (ref "IC19") (pin "43") (pinfunction "Q3_43") (pintype "output"))
      (node (ref "R69") (pin "2") (pinfunction "2_2") (pintype "passive"))
    )
    (net (code "41") (name "Net-(IC19-Q5)") (class "Default")
      (node (ref "C56") (pin "2") (pinfunction "2_2") (pintype "passive"))
      (node (ref "IC19") (pin "38") (pinfunction "Q5_38") (pintype "output"))
      (node (ref "R34") (pin "2") (pinfunction "2_2") (pintype "passive"))
    )
    (net (code "42") (name "Net-(IC19-Q6)") (class "Default")
      (node (ref "C65") (pin "2") (pinfunction "2_2") (pintype "passive"))
      (node (ref "IC19") (pin "36") (pinfunction "Q6_36") (pintype "output"))
      (node (ref "R71") (pin "2") (pinfunction "2_2") (pintype "passive"))
    )
    (net (code "43") (name "Net-(IC19-Q7)") (class "Default")
      (node (ref "C68") (pin "2") (pinfunction "2_2") (pintype "passive"))
      (node (ref "IC19") (pin "30") (pinfunction "Q7_30") (pintype "output"))
      (node (ref "R76") (pin "2") (pinfunction "2_2") (pintype "passive"))
    )
    (net (code "44") (name "Net-(IC19-Q8)") (class "Default")
      (node (ref "C95") (pin "2") (pinfunction "2_2") (pintype "passive"))
      (node (ref "IC19") (pin "27") (pinfunction "Q8_27") (pintype "output"))
      (node (ref "R101") (pin "2") (pinfunction "2_2") (pintype "passive"))
    )
    (net (code "45") (name "Net-(IC19-SFOUTA0)") (class "Default")
      (node (ref "IC19") (pin "2") (pinfunction "SFOUTA1_2") (pintype "input"))
      (node (ref "IC19") (pin "3") (pinfunction "SFOUTA0_3") (pintype "input"))
      (node (ref "IC19") (pin "31") (pinfunction "SFOUTB0_31") (pintype "input"))
      (node (ref "IC19") (pin "32") (pinfunction "SFOUTB1_32") (pintype "input"))
      (node (ref "R141") (pin "2") (pinfunction "2_2") (pintype "passive"))
    )
    (net (code "46") (name "Net-(IC19-VDD)") (class "Default")
      (node (ref "C100") (pin "2") (pinfunction "2_2") (pintype "passive"))
      (node (ref "C91") (pin "2") (pinfunction "2_2") (pintype "passive"))
      (node (ref "C97") (pin "2") (pinfunction "2_2") (pintype "passive"))
      (node (ref "C98") (pin "2") (pinfunction "2_2") (pintype "passive"))
      (node (ref "IC19") (pin "12") (pinfunction "VDD_12") (pintype "power_in"))
      (node (ref "IC19") (pin "34") (pinfunction "VDDOB_34") (pintype "power_in"))
      (node (ref "IC19") (pin "44") (pinfunction "VDDOA_44") (pintype "power_in"))
      (node (ref "L14") (pin "1") (pinfunction "1_1") (pintype "passive"))
      (node (ref "R103") (pin "1") (pinfunction "1_1") (pintype "passive"))
      (node (ref "R109") (pin "1") (pinfunction "1_1") (pintype "passive"))
      (node (ref "R151") (pin "2") (pinfunction "2_2") (pintype "passive"))
    )
    (net (code "47") (name "Net-(IC19-VREF)") (class "Default")
      (node (ref "C94") (pin "2") (pinfunction "2_2") (pintype "passive"))
      (node (ref "IC19") (pin "17") (pinfunction "VREF_17") (pintype "output"))
    )
    (net (code "48") (name "Net-(IC19-~{Q0})") (class "Default")
      (node (ref "C58") (pin "2") (pinfunction "2_2") (pintype "passive"))
      (node (ref "IC19") (pin "9") (pinfunction "~{Q0}_9") (pintype "output"))
      (node (ref "R37") (pin "2") (pinfunction "2_2") (pintype "passive"))
    )
    (net (code "49") (name "Net-(IC19-~{Q1})") (class "Default")
      (node (ref "C60") (pin "2") (pinfunction "2_2") (pintype "passive"))
      (node (ref "IC19") (pin "7") (pinfunction "~{Q1}_7") (pintype "output"))
      (node (ref "R61") (pin "2") (pinfunction "2_2") (pintype "passive"))
    )
    (net (code "50") (name "Net-(IC19-~{Q2})") (class "Default")
      (node (ref "C88") (pin "2") (pinfunction "2_2") (pintype "passive"))
      (node (ref "IC19") (pin "4") (pinfunction "~{Q2}_4") (pintype "output"))
      (node (ref "R63") (pin "2") (pinfunction "2_2") (pintype "passive"))
    )
    (net (code "51") (name "Net-(IC19-~{Q3})") (class "Default")
      (node (ref "C93") (pin "2") (pinfunction "2_2") (pintype "passive"))
      (node (ref "IC19") (pin "42") (pinfunction "~{Q3}_42") (pintype "output"))
      (node (ref "R77") (pin "2") (pinfunction "2_2") (pintype "passive"))
    )
    (net (code "52") (name "Net-(IC19-~{Q5})") (class "Default")
      (node (ref "C61") (pin "2") (pinfunction "2_2") (pintype "passive"))
      (node (ref "IC19") (pin "37") (pinfunction "~{Q5}_37") (pintype "output"))
      (node (ref "R70") (pin "2") (pinfunction "2_2") (pintype "passive"))
    )
    (net (code "53") (name "Net-(IC19-~{Q6})") (class "Default")
      (node (ref "C66") (pin "2") (pinfunction "2_2") (pintype "passive"))
      (node (ref "IC19") (pin "35") (pinfunction "~{Q6}_35") (pintype "output"))
      (node (ref "R72") (pin "2") (pinfunction "2_2") (pintype "passive"))
    )
    (net (code "54") (name "Net-(IC19-~{Q7})") (class "Default")
      (node (ref "C71") (pin "2") (pinfunction "2_2") (pintype "passive"))
      (node (ref "IC19") (pin "29") (pinfunction "~{Q7}_29") (pintype "output"))
      (node (ref "R95") (pin "2") (pinfunction "2_2") (pintype "passive"))
    )
    (net (code "55") (name "Net-(IC19-~{Q8})") (class "Default")
      (node (ref "C96") (pin "2") (pinfunction "2_2") (pintype "passive"))
      (node (ref "IC19") (pin "26") (pinfunction "~{Q8}_26") (pintype "output"))
      (node (ref "R102") (pin "2") (pinfunction "2_2") (pintype "passive"))
    )
    (net (code "56") (name "Net-(OSC1-OUT)") (class "Default")
      (node (ref "OSC1") (pin "3") (pinfunction "OUT_3") (pintype "output"))
      (node (ref "R117") (pin "2") (pinfunction "2_2") (pintype "passive"))
    )
    (net (code "57") (name "Net-(OSC1-VDD)") (class "Default")
      (node (ref "C101") (pin "2") (pinfunction "2_2") (pintype "passive"))
      (node (ref "C102") (pin "2") (pinfunction "2_2") (pintype "passive"))
      (node (ref "L9") (pin "1") (pinfunction "1_1") (pintype "passive"))
      (node (ref "OSC1") (pin "4") (pinfunction "VDD_4") (pintype "power_in"))
    )
    (net (code "58") (name "Net-(T1-D)") (class "Default")
      (node (ref "L9") (pin "2") (pinfunction "2_2") (pintype "passive"))
      (node (ref "T1") (pin "3") (pinfunction "D_3") (pintype "passive"))
    )
    (net (code "59") (name "P1V8A") (class "Default")
      (node (ref "R151") (pin "1") (pinfunction "1_1") (pintype "passive"))
    )
    (net (code "60") (name "P3V3A") (class "Default")
      (node (ref "L14") (pin "2") (pinfunction "2_2") (pintype "passive"))
      (node (ref "T1") (pin "2") (pinfunction "S_2") (pintype "passive"))
    )
    (net (code "61") (name "unconnected-(IC19-NC-Pad11)") (class "Default")
      (node (ref "IC19") (pin "11") (pinfunction "NC_11") (pintype "passive+no_connect"))
    )
    (net (code "62") (name "unconnected-(IC19-NC-Pad13)") (class "Default")
      (node (ref "IC19") (pin "13") (pinfunction "NC_13") (pintype "passive+no_connect"))
    )
    (net (code "63") (name "unconnected-(IC19-NC-Pad21)") (class "Default")
      (node (ref "IC19") (pin "21") (pinfunction "NC_21") (pintype "passive+no_connect"))
    )
    (net (code "64") (name "unconnected-(IC19-NC-Pad28)") (class "Default")
      (node (ref "IC19") (pin "28") (pinfunction "NC_28") (pintype "passive+no_connect"))
    )
    (net (code "65") (name "unconnected-(IC19-Q4-Pad41)") (class "Default")
      (node (ref "IC19") (pin "41") (pinfunction "Q4_41") (pintype "output+no_connect"))
    )
    (net (code "66") (name "unconnected-(IC19-Q9-Pad25)") (class "Default")
      (node (ref "IC19") (pin "25") (pinfunction "Q9_25") (pintype "output+no_connect"))
    )
    (net (code "67") (name "unconnected-(IC19-~{Q4}-Pad40)") (class "Default")
      (node (ref "IC19") (pin "40") (pinfunction "~{Q4}_40") (pintype "output+no_connect"))
    )
    (net (code "68") (name "unconnected-(IC19-~{Q9}-Pad24)") (class "Default")
      (node (ref "IC19") (pin "24") (pinfunction "~{Q9}_24") (pintype "output+no_connect"))
    )
    (net (code "69") (name "unconnected-(OSC1-NC-Pad1)") (class "Default")
      (node (ref "OSC1") (pin "1") (pinfunction "NC_1") (pintype "passive"))
    )
  )
)
